# 4_A_real_transistor.net
KiCad netlist of a schematic drawn in Altium Designer
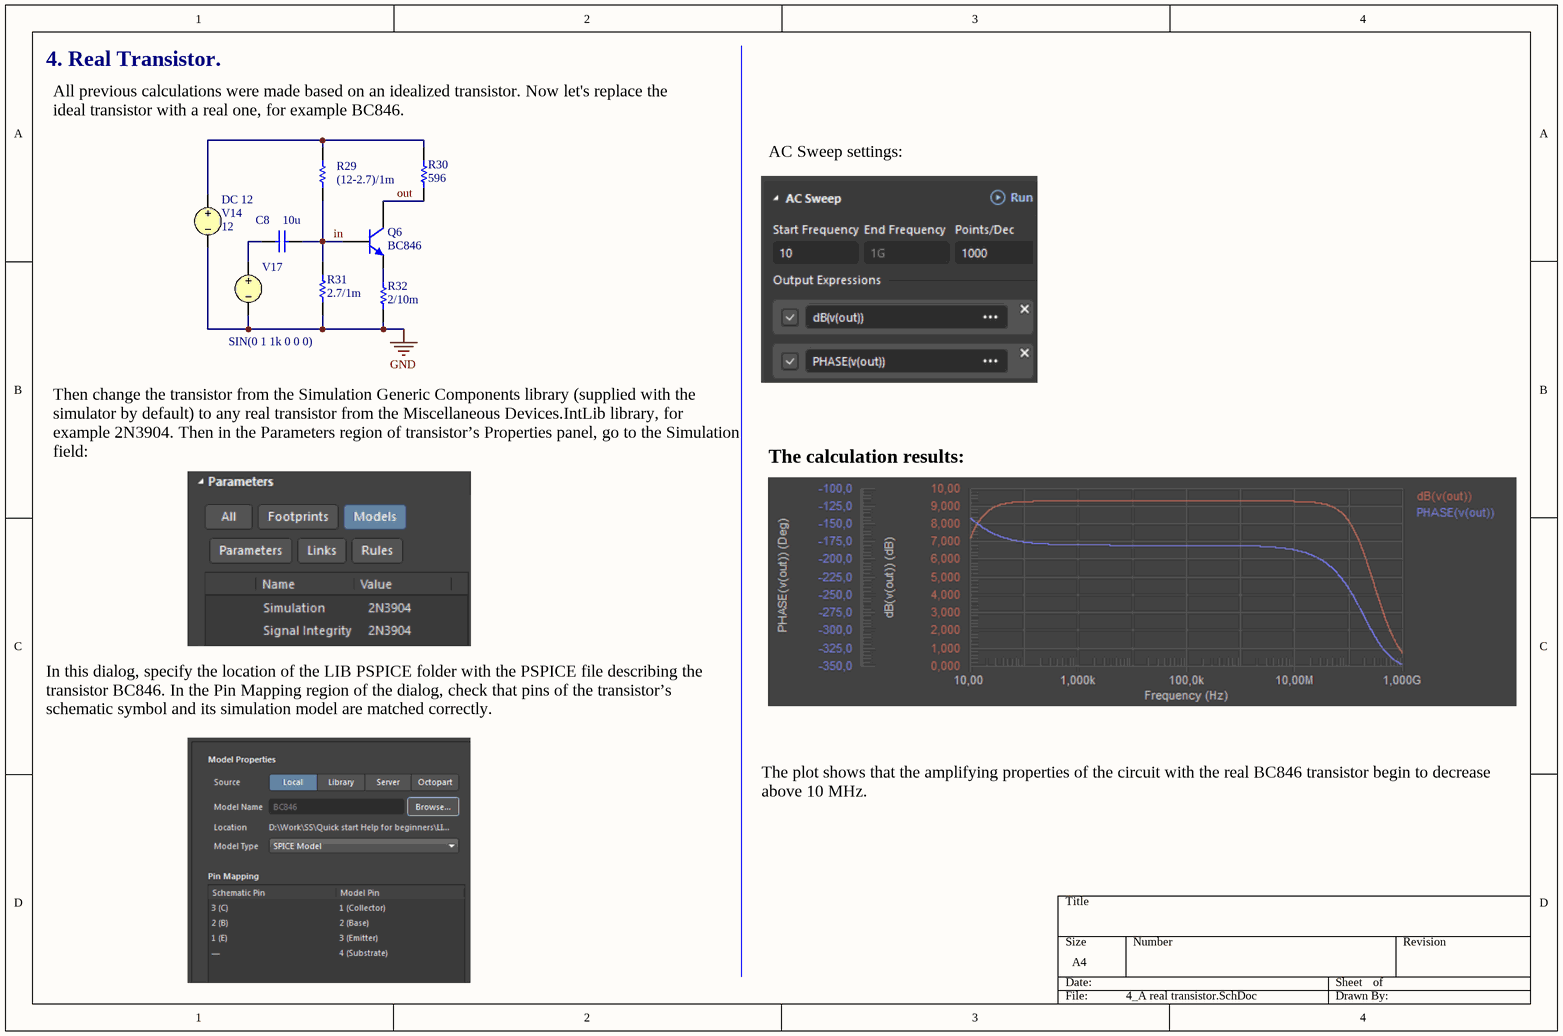
[diagram p0: 4_A real transistor.SchDoc]

(export (version "E")
  (design (tool "Eeschema 10.0.6"))
  (components
    (comp (ref "C8")
      (value "10u")
      (description "Capacitor")
      (libsource (lib "Simulation Generic Components") (part "Capacitor"))
    )
    (comp (ref "Q6")
      (value "BC846")
      (footprint "TO-92A")
      (description "NPN General Purpose Amplifier")
      (fields (field (name "PUBLISHER") "Altium Limited"))
      (libsource (lib "Miscellaneous Devices") (part "2N3904"))
    )
    (comp (ref "R29")
      (value "(12-2.7)/1m")
      (description "Resistor")
      (libsource (lib "Simulation Generic Components") (part "Resistor"))
    )
    (comp (ref "R30")
      (value "596")
      (description "Resistor")
      (libsource (lib "Simulation Generic Components") (part "Resistor"))
    )
    (comp (ref "R31")
      (value "2.7/1m")
      (description "Resistor")
      (libsource (lib "Simulation Generic Components") (part "Resistor"))
    )
    (comp (ref "R32")
      (value "2/10m")
      (description "Resistor")
      (libsource (lib "Simulation Generic Components") (part "Resistor"))
    )
    (comp (ref "V14")
      (value "DC 12")
      (description "Voltage Source")
      (fields (field (name "ALTIUM_VALUE") "12") (field (name "PUBLISHER") "Altium Limited"))
      (libsource (lib "Simulation Generic Components") (part "VSRC"))
    )
    (comp (ref "V17")
      (value "SIN(0 1 1k 0 0 0)")
      (description "Voltage Source")
      (fields (field (name "PUBLISHER") "Altium Limited"))
      (libsource (lib "Simulation Generic Components") (part "VSRC"))
    )
  )
  (nets
    (net (code "1") (name "/Vcc") (class "Default")
      (node (ref "R29") (pin "2") (pinfunction "2_2") (pintype "passive"))
      (node (ref "R30") (pin "2") (pinfunction "2_2") (pintype "passive"))
      (node (ref "V14") (pin "1") (pinfunction "1_1") (pintype "passive"))
    )
    (net (code "2") (name "/in") (class "Default")
      (node (ref "C8") (pin "2") (pinfunction "2_2") (pintype "passive"))
      (node (ref "Q6") (pin "2") (pinfunction "B_2") (pintype "passive"))
      (node (ref "R29") (pin "1") (pinfunction "1_1") (pintype "passive"))
      (node (ref "R31") (pin "1") (pinfunction "1_1") (pintype "passive"))
    )
    (net (code "3") (name "/out") (class "Default")
      (node (ref "Q6") (pin "3") (pinfunction "C_3") (pintype "passive"))
      (node (ref "R30") (pin "1") (pinfunction "1_1") (pintype "passive"))
    )
    (net (code "4") (name "GND") (class "Default")
      (node (ref "R31") (pin "2") (pinfunction "2_2") (pintype "passive"))
      (node (ref "R32") (pin "1") (pinfunction "1_1") (pintype "passive"))
      (node (ref "V14") (pin "2") (pinfunction "2_2") (pintype "passive"))
      (node (ref "V17") (pin "2") (pinfunction "2_2") (pintype "passive"))
    )
    (net (code "5") (name "Net-(C8-Pad1)") (class "Default")
      (node (ref "C8") (pin "1") (pinfunction "1_1") (pintype "passive"))
      (node (ref "V17") (pin "1") (pinfunction "1_1") (pintype "passive"))
    )
    (net (code "6") (name "Net-(Q6-E)") (class "Default")
      (node (ref "Q6") (pin "1") (pinfunction "E_1") (pintype "passive"))
      (node (ref "R32") (pin "2") (pinfunction "2_2") (pintype "passive"))
    )
  )
)
